# WorkFlowX_Final.net
KiCad netlist of a schematic drawn in EasyEDA Pro
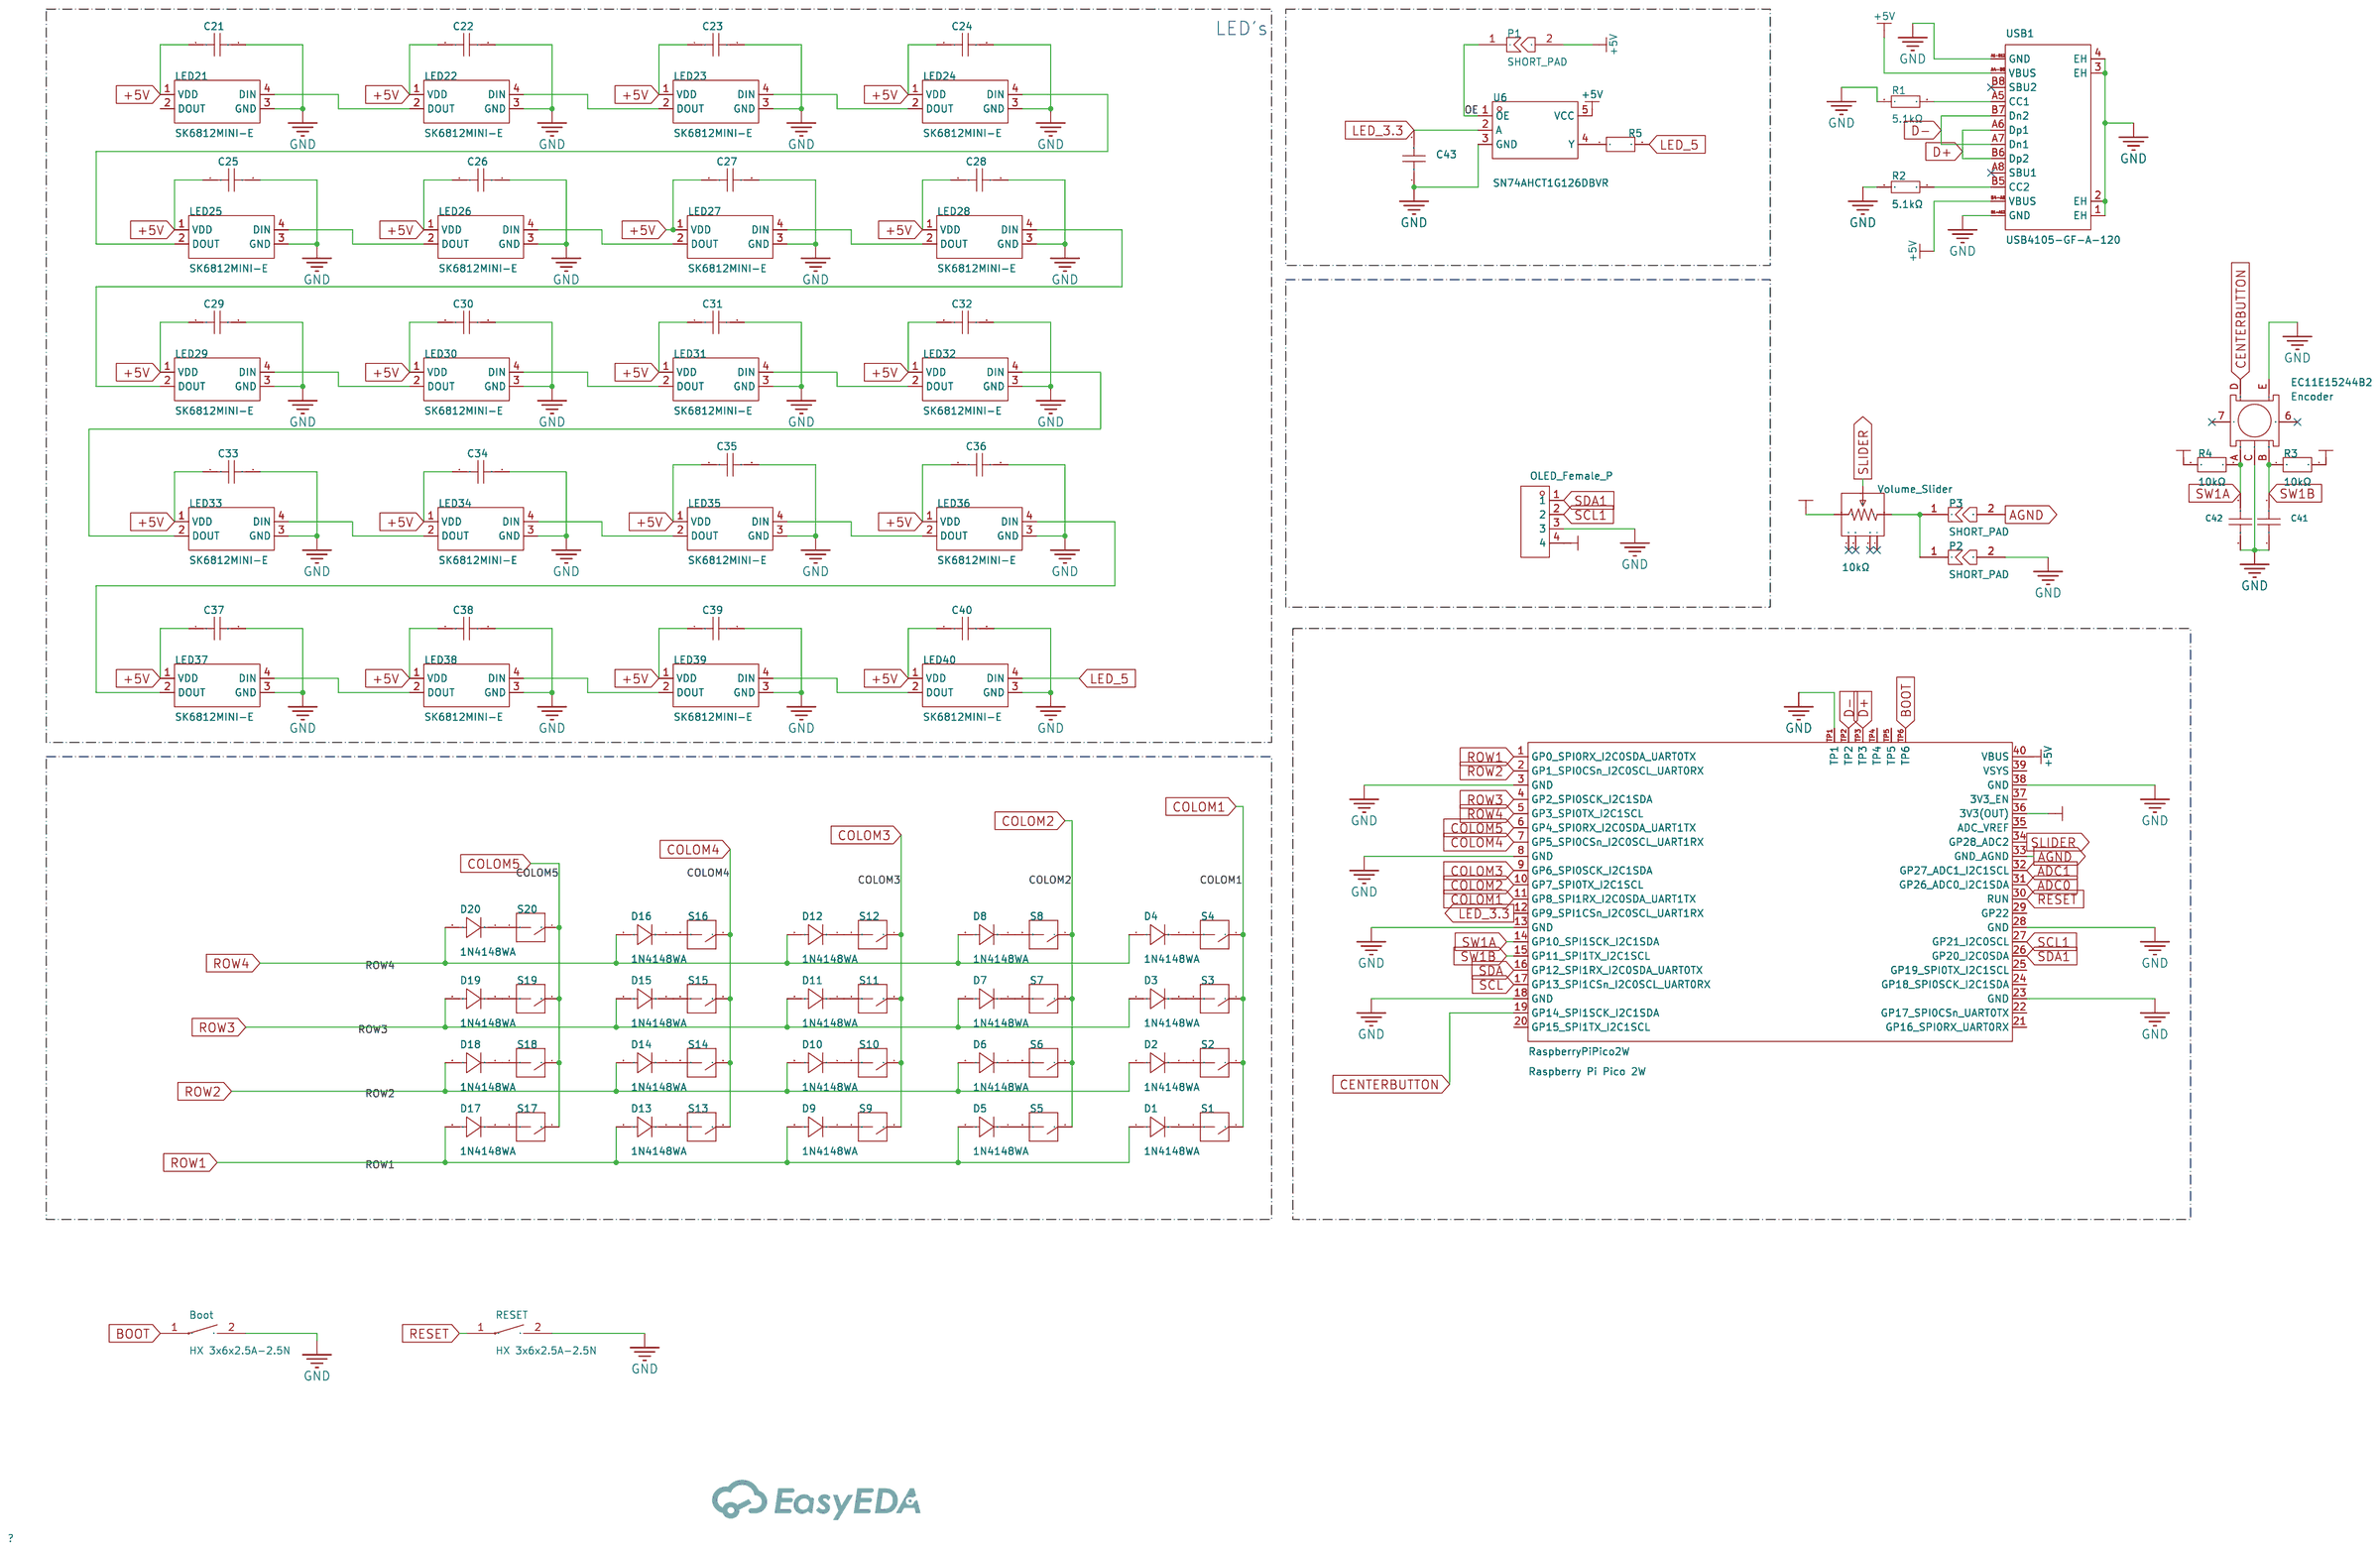
[diagram p0: schematic sheet]

(export (version "E")
  (design (tool "Eeschema 10.0.6"))
  (components
    (comp (ref "Boot")
      (value "HX 3x6x2.5A-2.5N")
      (footprint "easyedapro:SW-SMD_HX-TS-1101-C-W")
      (fields (field (name "Manufacturer") "hanxia(韩下)"))
      (libsource (lib "easyedapro") (part "HX TS-1101-C-W"))
    )
    (comp (ref "C21")
      (value "100nF")
      (footprint "easyedapro:C0603")
      (description "Capacitance:100nF Tolerance:±10% Tolerance:±10% Voltage Rating:50V Temperature Coefficient:X7R")
      (fields
        (field (name "Manufacturer Part") "CC0805KRX7R9BB104")
        (field (name "Manufacturer") "YAGEO(国巨)")
      )
      (libsource (lib "easyedapro") (part "NL0603B104M500CPBN"))
    )
    (comp (ref "C22")
      (value "100nF")
      (footprint "easyedapro:C0603")
      (description "Capacitance:100nF Tolerance:±10% Tolerance:±10% Voltage Rating:50V Temperature Coefficient:X7R")
      (fields
        (field (name "Manufacturer Part") "CC0805KRX7R9BB104")
        (field (name "Manufacturer") "YAGEO(国巨)")
      )
      (libsource (lib "easyedapro") (part "NL0603B104M500CPBN"))
    )
    (comp (ref "C23")
      (value "100nF")
      (footprint "easyedapro:C0603")
      (description "Capacitance:100nF Tolerance:±10% Tolerance:±10% Voltage Rating:50V Temperature Coefficient:X7R")
      (fields
        (field (name "Manufacturer Part") "CC0805KRX7R9BB104")
        (field (name "Manufacturer") "YAGEO(国巨)")
      )
      (libsource (lib "easyedapro") (part "NL0603B104M500CPBN"))
    )
    (comp (ref "C24")
      (value "100nF")
      (footprint "easyedapro:C0603")
      (description "Capacitance:100nF Tolerance:±10% Tolerance:±10% Voltage Rating:50V Temperature Coefficient:X7R")
      (fields
        (field (name "Manufacturer Part") "CC0805KRX7R9BB104")
        (field (name "Manufacturer") "YAGEO(国巨)")
      )
      (libsource (lib "easyedapro") (part "NL0603B104M500CPBN"))
    )
    (comp (ref "C25")
      (value "100nF")
      (footprint "easyedapro:C0603")
      (description "Capacitance:100nF Tolerance:±10% Tolerance:±10% Voltage Rating:50V Temperature Coefficient:X7R")
      (fields
        (field (name "Manufacturer Part") "CC0805KRX7R9BB104")
        (field (name "Manufacturer") "YAGEO(国巨)")
      )
      (libsource (lib "easyedapro") (part "NL0603B104M500CPBN"))
    )
    (comp (ref "C26")
      (value "100nF")
      (footprint "easyedapro:C0603")
      (description "Capacitance:100nF Tolerance:±10% Tolerance:±10% Voltage Rating:50V Temperature Coefficient:X7R")
      (fields
        (field (name "Manufacturer Part") "CC0805KRX7R9BB104")
        (field (name "Manufacturer") "YAGEO(国巨)")
      )
      (libsource (lib "easyedapro") (part "NL0603B104M500CPBN"))
    )
    (comp (ref "C27")
      (value "100nF")
      (footprint "easyedapro:C0603")
      (description "Capacitance:100nF Tolerance:±10% Tolerance:±10% Voltage Rating:50V Temperature Coefficient:X7R")
      (fields
        (field (name "Manufacturer Part") "CC0805KRX7R9BB104")
        (field (name "Manufacturer") "YAGEO(国巨)")
      )
      (libsource (lib "easyedapro") (part "NL0603B104M500CPBN"))
    )
    (comp (ref "C28")
      (value "100nF")
      (footprint "easyedapro:C0603")
      (description "Capacitance:100nF Tolerance:±10% Tolerance:±10% Voltage Rating:50V Temperature Coefficient:X7R")
      (fields
        (field (name "Manufacturer Part") "CC0805KRX7R9BB104")
        (field (name "Manufacturer") "YAGEO(国巨)")
      )
      (libsource (lib "easyedapro") (part "NL0603B104M500CPBN"))
    )
    (comp (ref "C29")
      (value "100nF")
      (footprint "easyedapro:C0603")
      (description "Capacitance:100nF Tolerance:±10% Tolerance:±10% Voltage Rating:50V Temperature Coefficient:X7R")
      (fields
        (field (name "Manufacturer Part") "CC0805KRX7R9BB104")
        (field (name "Manufacturer") "YAGEO(国巨)")
      )
      (libsource (lib "easyedapro") (part "NL0603B104M500CPBN"))
    )
    (comp (ref "C30")
      (value "100nF")
      (footprint "easyedapro:C0603")
      (description "Capacitance:100nF Tolerance:±10% Tolerance:±10% Voltage Rating:50V Temperature Coefficient:X7R")
      (fields
        (field (name "Manufacturer Part") "CC0805KRX7R9BB104")
        (field (name "Manufacturer") "YAGEO(国巨)")
      )
      (libsource (lib "easyedapro") (part "NL0603B104M500CPBN"))
    )
    (comp (ref "C31")
      (value "100nF")
      (footprint "easyedapro:C0603")
      (description "Capacitance:100nF Tolerance:±10% Tolerance:±10% Voltage Rating:50V Temperature Coefficient:X7R")
      (fields
        (field (name "Manufacturer Part") "CC0805KRX7R9BB104")
        (field (name "Manufacturer") "YAGEO(国巨)")
      )
      (libsource (lib "easyedapro") (part "NL0603B104M500CPBN"))
    )
    (comp (ref "C32")
      (value "100nF")
      (footprint "easyedapro:C0603")
      (description "Capacitance:100nF Tolerance:±10% Tolerance:±10% Voltage Rating:50V Temperature Coefficient:X7R")
      (fields
        (field (name "Manufacturer Part") "CC0805KRX7R9BB104")
        (field (name "Manufacturer") "YAGEO(国巨)")
      )
      (libsource (lib "easyedapro") (part "NL0603B104M500CPBN"))
    )
    (comp (ref "C33")
      (value "100nF")
      (footprint "easyedapro:C0603")
      (description "Capacitance:100nF Tolerance:±10% Tolerance:±10% Voltage Rating:50V Temperature Coefficient:X7R")
      (fields
        (field (name "Manufacturer Part") "CC0805KRX7R9BB104")
        (field (name "Manufacturer") "YAGEO(国巨)")
      )
      (libsource (lib "easyedapro") (part "NL0603B104M500CPBN"))
    )
    (comp (ref "C34")
      (value "100nF")
      (footprint "easyedapro:C0603")
      (description "Capacitance:100nF Tolerance:±10% Tolerance:±10% Voltage Rating:50V Temperature Coefficient:X7R")
      (fields
        (field (name "Manufacturer Part") "CC0805KRX7R9BB104")
        (field (name "Manufacturer") "YAGEO(国巨)")
      )
      (libsource (lib "easyedapro") (part "NL0603B104M500CPBN"))
    )
    (comp (ref "C35")
      (value "100nF")
      (footprint "easyedapro:C0603")
      (description "Capacitance:100nF Tolerance:±10% Tolerance:±10% Voltage Rating:50V Temperature Coefficient:X7R")
      (fields
        (field (name "Manufacturer Part") "CC0805KRX7R9BB104")
        (field (name "Manufacturer") "YAGEO(国巨)")
      )
      (libsource (lib "easyedapro") (part "NL0603B104M500CPBN"))
    )
    (comp (ref "C36")
      (value "100nF")
      (footprint "easyedapro:C0603")
      (description "Capacitance:100nF Tolerance:±10% Tolerance:±10% Voltage Rating:50V Temperature Coefficient:X7R")
      (fields
        (field (name "Manufacturer Part") "CC0805KRX7R9BB104")
        (field (name "Manufacturer") "YAGEO(国巨)")
      )
      (libsource (lib "easyedapro") (part "NL0603B104M500CPBN"))
    )
    (comp (ref "C37")
      (value "100nF")
      (footprint "easyedapro:C0603")
      (description "Capacitance:100nF Tolerance:±10% Tolerance:±10% Voltage Rating:50V Temperature Coefficient:X7R")
      (fields
        (field (name "Manufacturer Part") "CC0805KRX7R9BB104")
        (field (name "Manufacturer") "YAGEO(国巨)")
      )
      (libsource (lib "easyedapro") (part "NL0603B104M500CPBN"))
    )
    (comp (ref "C38")
      (value "100nF")
      (footprint "easyedapro:C0603")
      (description "Capacitance:100nF Tolerance:±10% Tolerance:±10% Voltage Rating:50V Temperature Coefficient:X7R")
      (fields
        (field (name "Manufacturer Part") "CC0805KRX7R9BB104")
        (field (name "Manufacturer") "YAGEO(国巨)")
      )
      (libsource (lib "easyedapro") (part "NL0603B104M500CPBN"))
    )
    (comp (ref "C39")
      (value "100nF")
      (footprint "easyedapro:C0603")
      (description "Capacitance:100nF Tolerance:±10% Tolerance:±10% Voltage Rating:50V Temperature Coefficient:X7R")
      (fields
        (field (name "Manufacturer Part") "CC0805KRX7R9BB104")
        (field (name "Manufacturer") "YAGEO(国巨)")
      )
      (libsource (lib "easyedapro") (part "NL0603B104M500CPBN"))
    )
    (comp (ref "C40")
      (value "100nF")
      (footprint "easyedapro:C0603")
      (description "Capacitance:100nF Tolerance:±10% Tolerance:±10% Voltage Rating:50V Temperature Coefficient:X7R")
      (fields
        (field (name "Manufacturer Part") "CC0805KRX7R9BB104")
        (field (name "Manufacturer") "YAGEO(国巨)")
      )
      (libsource (lib "easyedapro") (part "NL0603B104M500CPBN"))
    )
    (comp (ref "C41")
      (value "100nF")
      (footprint "easyedapro:C0805")
      (description "Capacitance:100nF Tolerance:±10% Tolerance:±10% Voltage Rating:50V Temperature Coefficient:X7R")
      (fields
        (field (name "Manufacturer Part") "CC0805KRX7R9BB104")
        (field (name "Manufacturer") "YAGEO(国巨)")
      )
      (libsource (lib "easyedapro") (part "CC0805JRX7R9BB103"))
    )
    (comp (ref "C42")
      (value "100nF")
      (footprint "easyedapro:C0805")
      (description "Capacitance:100nF Tolerance:±10% Tolerance:±10% Voltage Rating:50V Temperature Coefficient:X7R")
      (fields
        (field (name "Manufacturer Part") "CC0805KRX7R9BB104")
        (field (name "Manufacturer") "YAGEO(国巨)")
      )
      (libsource (lib "easyedapro") (part "CC0805JRX7R9BB103"))
    )
    (comp (ref "C43")
      (value "100nF")
      (footprint "easyedapro:C0603")
      (description "Capacitance:100nF Tolerance:±10% Tolerance:±10% Voltage Rating:50V Temperature Coefficient:X7R")
      (fields
        (field (name "Manufacturer Part") "CC0805KRX7R9BB104")
        (field (name "Manufacturer") "YAGEO(国巨)")
      )
      (libsource (lib "easyedapro") (part "NL0603B104M500CPBN"))
    )
    (comp (ref "D1")
      (value "1N4148WA")
      (footprint "easyedapro:SOD-323_L1.7-W1.3-LS2.7-RD")
      (fields (field (name "Manufacturer") "PJSEMI(平晶微)"))
      (libsource (lib "easyedapro") (part "1N4148WS_C5381436"))
    )
    (comp (ref "D2")
      (value "1N4148WA")
      (footprint "easyedapro:SOD-323_L1.7-W1.3-LS2.7-RD")
      (fields (field (name "Manufacturer") "PJSEMI(平晶微)"))
      (libsource (lib "easyedapro") (part "1N4148WS_C5381436"))
    )
    (comp (ref "D3")
      (value "1N4148WA")
      (footprint "easyedapro:SOD-323_L1.7-W1.3-LS2.7-RD")
      (fields (field (name "Manufacturer") "PJSEMI(平晶微)"))
      (libsource (lib "easyedapro") (part "1N4148WS_C5381436"))
    )
    (comp (ref "D4")
      (value "1N4148WA")
      (footprint "easyedapro:SOD-323_L1.7-W1.3-LS2.7-RD")
      (fields (field (name "Manufacturer") "PJSEMI(平晶微)"))
      (libsource (lib "easyedapro") (part "1N4148WS_C5381436"))
    )
    (comp (ref "D5")
      (value "1N4148WA")
      (footprint "easyedapro:SOD-323_L1.7-W1.3-LS2.7-RD")
      (fields (field (name "Manufacturer") "PJSEMI(平晶微)"))
      (libsource (lib "easyedapro") (part "1N4148WS_C5381436"))
    )
    (comp (ref "D6")
      (value "1N4148WA")
      (footprint "easyedapro:SOD-323_L1.7-W1.3-LS2.7-RD")
      (fields (field (name "Manufacturer") "PJSEMI(平晶微)"))
      (libsource (lib "easyedapro") (part "1N4148WS_C5381436"))
    )
    (comp (ref "D7")
      (value "1N4148WA")
      (footprint "easyedapro:SOD-323_L1.7-W1.3-LS2.7-RD")
      (fields (field (name "Manufacturer") "PJSEMI(平晶微)"))
      (libsource (lib "easyedapro") (part "1N4148WS_C5381436"))
    )
    (comp (ref "D8")
      (value "1N4148WA")
      (footprint "easyedapro:SOD-323_L1.7-W1.3-LS2.7-RD")
      (fields (field (name "Manufacturer") "PJSEMI(平晶微)"))
      (libsource (lib "easyedapro") (part "1N4148WS_C5381436"))
    )
    (comp (ref "D9")
      (value "1N4148WA")
      (footprint "easyedapro:SOD-323_L1.7-W1.3-LS2.7-RD")
      (fields (field (name "Manufacturer") "PJSEMI(平晶微)"))
      (libsource (lib "easyedapro") (part "1N4148WS_C5381436"))
    )
    (comp (ref "D10")
      (value "1N4148WA")
      (footprint "easyedapro:SOD-323_L1.7-W1.3-LS2.7-RD")
      (fields (field (name "Manufacturer") "PJSEMI(平晶微)"))
      (libsource (lib "easyedapro") (part "1N4148WS_C5381436"))
    )
    (comp (ref "D11")
      (value "1N4148WA")
      (footprint "easyedapro:SOD-323_L1.7-W1.3-LS2.7-RD")
      (fields (field (name "Manufacturer") "PJSEMI(平晶微)"))
      (libsource (lib "easyedapro") (part "1N4148WS_C5381436"))
    )
    (comp (ref "D12")
      (value "1N4148WA")
      (footprint "easyedapro:SOD-323_L1.7-W1.3-LS2.7-RD")
      (fields (field (name "Manufacturer") "PJSEMI(平晶微)"))
      (libsource (lib "easyedapro") (part "1N4148WS_C5381436"))
    )
    (comp (ref "D13")
      (value "1N4148WA")
      (footprint "easyedapro:SOD-323_L1.7-W1.3-LS2.7-RD")
      (fields (field (name "Manufacturer") "PJSEMI(平晶微)"))
      (libsource (lib "easyedapro") (part "1N4148WS_C5381436"))
    )
    (comp (ref "D14")
      (value "1N4148WA")
      (footprint "easyedapro:SOD-323_L1.7-W1.3-LS2.7-RD")
      (fields (field (name "Manufacturer") "PJSEMI(平晶微)"))
      (libsource (lib "easyedapro") (part "1N4148WS_C5381436"))
    )
    (comp (ref "D15")
      (value "1N4148WA")
      (footprint "easyedapro:SOD-323_L1.7-W1.3-LS2.7-RD")
      (fields (field (name "Manufacturer") "PJSEMI(平晶微)"))
      (libsource (lib "easyedapro") (part "1N4148WS_C5381436"))
    )
    (comp (ref "D16")
      (value "1N4148WA")
      (footprint "easyedapro:SOD-323_L1.7-W1.3-LS2.7-RD")
      (fields (field (name "Manufacturer") "PJSEMI(平晶微)"))
      (libsource (lib "easyedapro") (part "1N4148WS_C5381436"))
    )
    (comp (ref "D17")
      (value "1N4148WA")
      (footprint "easyedapro:SOD-323_L1.7-W1.3-LS2.7-RD")
      (fields (field (name "Manufacturer") "PJSEMI(平晶微)"))
      (libsource (lib "easyedapro") (part "1N4148WS_C5381436"))
    )
    (comp (ref "D18")
      (value "1N4148WA")
      (footprint "easyedapro:SOD-323_L1.7-W1.3-LS2.7-RD")
      (fields (field (name "Manufacturer") "PJSEMI(平晶微)"))
      (libsource (lib "easyedapro") (part "1N4148WS_C5381436"))
    )
    (comp (ref "D19")
      (value "1N4148WA")
      (footprint "easyedapro:SOD-323_L1.7-W1.3-LS2.7-RD")
      (fields (field (name "Manufacturer") "PJSEMI(平晶微)"))
      (libsource (lib "easyedapro") (part "1N4148WS_C5381436"))
    )
    (comp (ref "D20")
      (value "1N4148WA")
      (footprint "easyedapro:SOD-323_L1.7-W1.3-LS2.7-RD")
      (fields (field (name "Manufacturer") "PJSEMI(平晶微)"))
      (libsource (lib "easyedapro") (part "1N4148WS_C5381436"))
    )
    (comp (ref "Encoder")
      (value "EC11E15244B2")
      (footprint "easyedapro:SW-TH_EC11XXXXXXXX")
      (fields (field (name "Manufacturer") "ALPSALPINE(阿尔卑斯阿尔派)"))
      (libsource (lib "easyedapro") (part "EC11E15204A3"))
    )
    (comp (ref "LED21")
      (value "SK6812MINI-E")
      (footprint "easyedapro:LED-SMD_L3.2-W2.8-LS5.9_SK6812MINI-E")
      (fields (field (name "Manufacturer") "欧思科光电"))
      (libsource (lib "easyedapro") (part "SK6812MINI-E_C5149201"))
    )
    (comp (ref "LED22")
      (value "SK6812MINI-E")
      (footprint "easyedapro:LED-SMD_L3.2-W2.8-LS5.9_SK6812MINI-E")
      (fields (field (name "Manufacturer") "欧思科光电"))
      (libsource (lib "easyedapro") (part "SK6812MINI-E_C5149201"))
    )
    (comp (ref "LED23")
      (value "SK6812MINI-E")
      (footprint "easyedapro:LED-SMD_L3.2-W2.8-LS5.9_SK6812MINI-E")
      (fields (field (name "Manufacturer") "欧思科光电"))
      (libsource (lib "easyedapro") (part "SK6812MINI-E_C5149201"))
    )
    (comp (ref "LED24")
      (value "SK6812MINI-E")
      (footprint "easyedapro:LED-SMD_L3.2-W2.8-LS5.9_SK6812MINI-E")
      (fields (field (name "Manufacturer") "欧思科光电"))
      (libsource (lib "easyedapro") (part "SK6812MINI-E_C5149201"))
    )
    (comp (ref "LED25")
      (value "SK6812MINI-E")
      (footprint "easyedapro:LED-SMD_L3.2-W2.8-LS5.9_SK6812MINI-E")
      (fields (field (name "Manufacturer") "欧思科光电"))
      (libsource (lib "easyedapro") (part "SK6812MINI-E_C5149201"))
    )
    (comp (ref "LED26")
      (value "SK6812MINI-E")
      (footprint "easyedapro:LED-SMD_L3.2-W2.8-LS5.9_SK6812MINI-E")
      (fields (field (name "Manufacturer") "欧思科光电"))
      (libsource (lib "easyedapro") (part "SK6812MINI-E_C5149201"))
    )
    (comp (ref "LED27")
      (value "SK6812MINI-E")
      (footprint "easyedapro:LED-SMD_L3.2-W2.8-LS5.9_SK6812MINI-E")
      (fields (field (name "Manufacturer") "欧思科光电"))
      (libsource (lib "easyedapro") (part "SK6812MINI-E_C5149201"))
    )
    (comp (ref "LED28")
      (value "SK6812MINI-E")
      (footprint "easyedapro:LED-SMD_L3.2-W2.8-LS5.9_SK6812MINI-E")
      (fields (field (name "Manufacturer") "欧思科光电"))
      (libsource (lib "easyedapro") (part "SK6812MINI-E_C5149201"))
    )
    (comp (ref "LED29")
      (value "SK6812MINI-E")
      (footprint "easyedapro:LED-SMD_L3.2-W2.8-LS5.9_SK6812MINI-E")
      (fields (field (name "Manufacturer") "欧思科光电"))
      (libsource (lib "easyedapro") (part "SK6812MINI-E_C5149201"))
    )
    (comp (ref "LED30")
      (value "SK6812MINI-E")
      (footprint "easyedapro:LED-SMD_L3.2-W2.8-LS5.9_SK6812MINI-E")
      (fields (field (name "Manufacturer") "欧思科光电"))
      (libsource (lib "easyedapro") (part "SK6812MINI-E_C5149201"))
    )
    (comp (ref "LED31")
      (value "SK6812MINI-E")
      (footprint "easyedapro:LED-SMD_L3.2-W2.8-LS5.9_SK6812MINI-E")
      (fields (field (name "Manufacturer") "欧思科光电"))
      (libsource (lib "easyedapro") (part "SK6812MINI-E_C5149201"))
    )
    (comp (ref "LED32")
      (value "SK6812MINI-E")
      (footprint "easyedapro:LED-SMD_L3.2-W2.8-LS5.9_SK6812MINI-E")
      (fields (field (name "Manufacturer") "欧思科光电"))
      (libsource (lib "easyedapro") (part "SK6812MINI-E_C5149201"))
    )
    (comp (ref "LED33")
      (value "SK6812MINI-E")
      (footprint "easyedapro:LED-SMD_L3.2-W2.8-LS5.9_SK6812MINI-E")
      (fields (field (name "Manufacturer") "欧思科光电"))
      (libsource (lib "easyedapro") (part "SK6812MINI-E_C5149201"))
    )
    (comp (ref "LED34")
      (value "SK6812MINI-E")
      (footprint "easyedapro:LED-SMD_L3.2-W2.8-LS5.9_SK6812MINI-E")
      (fields (field (name "Manufacturer") "欧思科光电"))
      (libsource (lib "easyedapro") (part "SK6812MINI-E_C5149201"))
    )
    (comp (ref "LED35")
      (value "SK6812MINI-E")
      (footprint "easyedapro:LED-SMD_L3.2-W2.8-LS5.9_SK6812MINI-E")
      (fields (field (name "Manufacturer") "欧思科光电"))
      (libsource (lib "easyedapro") (part "SK6812MINI-E_C5149201"))
    )
    (comp (ref "LED36")
      (value "SK6812MINI-E")
      (footprint "easyedapro:LED-SMD_L3.2-W2.8-LS5.9_SK6812MINI-E")
      (fields (field (name "Manufacturer") "欧思科光电"))
      (libsource (lib "easyedapro") (part "SK6812MINI-E_C5149201"))
    )
    (comp (ref "LED37")
      (value "SK6812MINI-E")
      (footprint "easyedapro:LED-SMD_L3.2-W2.8-LS5.9_SK6812MINI-E")
      (fields (field (name "Manufacturer") "欧思科光电"))
      (libsource (lib "easyedapro") (part "SK6812MINI-E_C5149201"))
    )
    (comp (ref "LED38")
      (value "SK6812MINI-E")
      (footprint "easyedapro:LED-SMD_L3.2-W2.8-LS5.9_SK6812MINI-E")
      (fields (field (name "Manufacturer") "欧思科光电"))
      (libsource (lib "easyedapro") (part "SK6812MINI-E_C5149201"))
    )
    (comp (ref "LED39")
      (value "SK6812MINI-E")
      (footprint "easyedapro:LED-SMD_L3.2-W2.8-LS5.9_SK6812MINI-E")
      (fields (field (name "Manufacturer") "欧思科光电"))
      (libsource (lib "easyedapro") (part "SK6812MINI-E_C5149201"))
    )
    (comp (ref "LED40")
      (value "SK6812MINI-E")
      (footprint "easyedapro:LED-SMD_L3.2-W2.8-LS5.9_SK6812MINI-E")
      (fields (field (name "Manufacturer") "欧思科光电"))
      (libsource (lib "easyedapro") (part "SK6812MINI-E_C5149201"))
    )
    (comp (ref "OLED_Female_P")
      (value "~")
      (footprint "easyedapro:CONN-TH_4P-P2.50-XH2.54-4P")
      (fields (field (name "Manufacturer Part") "XH-2.54-4P"))
      (libsource (lib "easyedapro") (part "XH-2.54-4P"))
    )
    (comp (ref "P1")
      (value "SHORT_PAD")
      (footprint "easyedapro:SHORT_PAD")
      (libsource (lib "easyedapro") (part "SHORT_PAD"))
    )
    (comp (ref "P2")
      (value "SHORT_PAD")
      (footprint "easyedapro:SHORT_PAD")
      (libsource (lib "easyedapro") (part "SHORT_PAD"))
    )
    (comp (ref "P3")
      (value "SHORT_PAD")
      (footprint "easyedapro:SHORT_PAD")
      (libsource (lib "easyedapro") (part "SHORT_PAD"))
    )
    (comp (ref "R1")
      (value "5.1kΩ")
      (footprint "easyedapro:R0805")
      (fields (field (name "Manufacturer Part") "MCR10EZPF5101") (field (name "Manufacturer") "ROHM(罗姆)"))
      (libsource (lib "easyedapro") (part "MCR10EZPF5101"))
    )
    (comp (ref "R2")
      (value "5.1kΩ")
      (footprint "easyedapro:R0805")
      (fields (field (name "Manufacturer Part") "MCR10EZPF5101") (field (name "Manufacturer") "ROHM(罗姆)"))
      (libsource (lib "easyedapro") (part "MCR10EZPF5101"))
    )
    (comp (ref "R3")
      (value "10kΩ")
      (footprint "easyedapro:R0805")
      (fields (field (name "Manufacturer Part") "SCR0805J10K") (field (name "Manufacturer") "VO(翔胜)"))
      (libsource (lib "easyedapro") (part "SCR0805J10K"))
    )
    (comp (ref "R4")
      (value "10kΩ")
      (footprint "easyedapro:R0805")
      (fields (field (name "Manufacturer Part") "SCR0805J10K") (field (name "Manufacturer") "VO(翔胜)"))
      (libsource (lib "easyedapro") (part "SCR0805J10K"))
    )
    (comp (ref "R5")
      (value "300Ω")
      (footprint "easyedapro:R0805")
      (fields
        (field (name "Manufacturer Part") "CRCW0805300RFKEA")
        (field (name "Manufacturer") "VISHAY(威世)")
      )
      (libsource (lib "easyedapro") (part "CRCW0805300RFKEA"))
    )
    (comp (ref "RaspberryPiPico2W")
      (value "Raspberry Pi Pico 2W")
      (footprint "easyedapro:COMM-SMD_L51.0-W21.0-P2.54_PICOW")
      (fields (field (name "Manufacturer") "Raspberry Pi(树莓派)"))
      (libsource (lib "easyedapro") (part "RASPBERRY PI PICO 2W"))
    )
    (comp (ref "RESET")
      (value "HX 3x6x2.5A-2.5N")
      (footprint "easyedapro:SW-SMD_HX-TS-1101-C-W")
      (fields (field (name "Manufacturer") "hanxia(韩下)"))
      (libsource (lib "easyedapro") (part "HX TS-1101-C-W"))
    )
    (comp (ref "S1")
      (value "adafruit_electromech_KBD_SWITCH_KAILH_SOCKET_BOX_JADE_KAILH_SOCKET")
      (footprint "easyedapro:KAILH_SOCKET")
      (libsource (lib "easyedapro") (part "adafruit_electromech_KBD_SWITCH_KAILH_SOCKET_BOX_JADE_KAILH_SOCKET"))
    )
    (comp (ref "S2")
      (value "adafruit_electromech_KBD_SWITCH_KAILH_SOCKET_BOX_JADE_KAILH_SOCKET")
      (footprint "easyedapro:KAILH_SOCKET")
      (libsource (lib "easyedapro") (part "adafruit_electromech_KBD_SWITCH_KAILH_SOCKET_BOX_JADE_KAILH_SOCKET"))
    )
    (comp (ref "S3")
      (value "adafruit_electromech_KBD_SWITCH_KAILH_SOCKET_BOX_JADE_KAILH_SOCKET")
      (footprint "easyedapro:KAILH_SOCKET")
      (libsource (lib "easyedapro") (part "adafruit_electromech_KBD_SWITCH_KAILH_SOCKET_BOX_JADE_KAILH_SOCKET"))
    )
    (comp (ref "S4")
      (value "adafruit_electromech_KBD_SWITCH_KAILH_SOCKET_BOX_JADE_KAILH_SOCKET")
      (footprint "easyedapro:KAILH_SOCKET")
      (libsource (lib "easyedapro") (part "adafruit_electromech_KBD_SWITCH_KAILH_SOCKET_BOX_JADE_KAILH_SOCKET"))
    )
    (comp (ref "S5")
      (value "adafruit_electromech_KBD_SWITCH_KAILH_SOCKET_BOX_JADE_KAILH_SOCKET")
      (footprint "easyedapro:KAILH_SOCKET")
      (libsource (lib "easyedapro") (part "adafruit_electromech_KBD_SWITCH_KAILH_SOCKET_BOX_JADE_KAILH_SOCKET"))
    )
    (comp (ref "S6")
      (value "adafruit_electromech_KBD_SWITCH_KAILH_SOCKET_BOX_JADE_KAILH_SOCKET")
      (footprint "easyedapro:KAILH_SOCKET")
      (libsource (lib "easyedapro") (part "adafruit_electromech_KBD_SWITCH_KAILH_SOCKET_BOX_JADE_KAILH_SOCKET"))
    )
    (comp (ref "S7")
      (value "adafruit_electromech_KBD_SWITCH_KAILH_SOCKET_BOX_JADE_KAILH_SOCKET")
      (footprint "easyedapro:KAILH_SOCKET")
      (libsource (lib "easyedapro") (part "adafruit_electromech_KBD_SWITCH_KAILH_SOCKET_BOX_JADE_KAILH_SOCKET"))
    )
    (comp (ref "S8")
      (value "adafruit_electromech_KBD_SWITCH_KAILH_SOCKET_BOX_JADE_KAILH_SOCKET")
      (footprint "easyedapro:KAILH_SOCKET")
      (libsource (lib "easyedapro") (part "adafruit_electromech_KBD_SWITCH_KAILH_SOCKET_BOX_JADE_KAILH_SOCKET"))
    )
    (comp (ref "S9")
      (value "adafruit_electromech_KBD_SWITCH_KAILH_SOCKET_BOX_JADE_KAILH_SOCKET")
      (footprint "easyedapro:KAILH_SOCKET")
      (libsource (lib "easyedapro") (part "adafruit_electromech_KBD_SWITCH_KAILH_SOCKET_BOX_JADE_KAILH_SOCKET"))
    )
    (comp (ref "S10")
      (value "adafruit_electromech_KBD_SWITCH_KAILH_SOCKET_BOX_JADE_KAILH_SOCKET")
      (footprint "easyedapro:KAILH_SOCKET")
      (libsource (lib "easyedapro") (part "adafruit_electromech_KBD_SWITCH_KAILH_SOCKET_BOX_JADE_KAILH_SOCKET"))
    )
    (comp (ref "S11")
      (value "adafruit_electromech_KBD_SWITCH_KAILH_SOCKET_BOX_JADE_KAILH_SOCKET")
      (footprint "easyedapro:KAILH_SOCKET")
      (libsource (lib "easyedapro") (part "adafruit_electromech_KBD_SWITCH_KAILH_SOCKET_BOX_JADE_KAILH_SOCKET"))
    )
    (comp (ref "S12")
      (value "adafruit_electromech_KBD_SWITCH_KAILH_SOCKET_BOX_JADE_KAILH_SOCKET")
      (footprint "easyedapro:KAILH_SOCKET")
      (libsource (lib "easyedapro") (part "adafruit_electromech_KBD_SWITCH_KAILH_SOCKET_BOX_JADE_KAILH_SOCKET"))
    )
    (comp (ref "S13")
      (value "adafruit_electromech_KBD_SWITCH_KAILH_SOCKET_BOX_JADE_KAILH_SOCKET")
      (footprint "easyedapro:KAILH_SOCKET")
      (libsource (lib "easyedapro") (part "adafruit_electromech_KBD_SWITCH_KAILH_SOCKET_BOX_JADE_KAILH_SOCKET"))
    )
    (comp (ref "S14")
      (value "adafruit_electromech_KBD_SWITCH_KAILH_SOCKET_BOX_JADE_KAILH_SOCKET")
      (footprint "easyedapro:KAILH_SOCKET")
      (libsource (lib "easyedapro") (part "adafruit_electromech_KBD_SWITCH_KAILH_SOCKET_BOX_JADE_KAILH_SOCKET"))
    )
    (comp (ref "S15")
      (value "adafruit_electromech_KBD_SWITCH_KAILH_SOCKET_BOX_JADE_KAILH_SOCKET")
      (footprint "easyedapro:KAILH_SOCKET")
      (libsource (lib "easyedapro") (part "adafruit_electromech_KBD_SWITCH_KAILH_SOCKET_BOX_JADE_KAILH_SOCKET"))
    )
    (comp (ref "S16")
      (value "adafruit_electromech_KBD_SWITCH_KAILH_SOCKET_BOX_JADE_KAILH_SOCKET")
      (footprint "easyedapro:KAILH_SOCKET")
      (libsource (lib "easyedapro") (part "adafruit_electromech_KBD_SWITCH_KAILH_SOCKET_BOX_JADE_KAILH_SOCKET"))
    )
    (comp (ref "S17")
      (value "adafruit_electromech_KBD_SWITCH_KAILH_SOCKET_BOX_JADE_KAILH_SOCKET")
      (footprint "easyedapro:KAILH_SOCKET")
      (libsource (lib "easyedapro") (part "adafruit_electromech_KBD_SWITCH_KAILH_SOCKET_BOX_JADE_KAILH_SOCKET"))
    )
    (comp (ref "S18")
      (value "adafruit_electromech_KBD_SWITCH_KAILH_SOCKET_BOX_JADE_KAILH_SOCKET")
      (footprint "easyedapro:KAILH_SOCKET")
      (libsource (lib "easyedapro") (part "adafruit_electromech_KBD_SWITCH_KAILH_SOCKET_BOX_JADE_KAILH_SOCKET"))
    )
    (comp (ref "S19")
      (value "adafruit_electromech_KBD_SWITCH_KAILH_SOCKET_BOX_JADE_KAILH_SOCKET")
      (footprint "easyedapro:KAILH_SOCKET")
      (libsource (lib "easyedapro") (part "adafruit_electromech_KBD_SWITCH_KAILH_SOCKET_BOX_JADE_KAILH_SOCKET"))
    )
    (comp (ref "S20")
      (value "adafruit_electromech_KBD_SWITCH_KAILH_SOCKET_BOX_JADE_KAILH_SOCKET")
      (footprint "easyedapro:KAILH_SOCKET")
      (libsource (lib "easyedapro") (part "adafruit_electromech_KBD_SWITCH_KAILH_SOCKET_BOX_JADE_KAILH_SOCKET"))
    )
    (comp (ref "U6")
      (value "SN74AHCT1G126DBVR")
      (footprint "easyedapro:SOT-23-5_L3.0-W1.7-P0.95-LS2.8-BR")
      (fields (field (name "Manufacturer") "TI(德州仪器)"))
      (libsource (lib "easyedapro") (part "SN74AHCT1G126DBVR"))
    )
    (comp (ref "USB1")
      (value "USB4105-GF-A-120")
      (footprint "easyedapro:USB-C-SMD_MC-311D")
      (fields (field (name "Manufacturer") "GCT"))
      (libsource (lib "easyedapro") (part "USB4105-GF-A-120"))
    )
    (comp (ref "Volume_Slider")
      (value "10kΩ")
      (footprint "easyedapro:RES-ADJ-TH_PTA6043-2015DPB103")
      (description "Resistance:10kΩ Tolerance:±20% Tolerance:±20% Power(Watts):250mW")
      (fields (field (name "Manufacturer Part") "PTA6043-2015DPB103") (field (name "Manufacturer") "BOURNS"))
      (libsource (lib "easyedapro") (part "PTA6043-2015DPB103"))
    )
  )
  (nets
    (net (code "1") (name "+3.3V") (class "Default")
      (node (ref "OLED_Female_P") (pin "4") (pinfunction "4_4") (pintype "input"))
      (node (ref "R3") (pin "2") (pinfunction "2_2") (pintype "unspecified"))
      (node (ref "R4") (pin "1") (pinfunction "1_1") (pintype "unspecified"))
      (node (ref "RaspberryPiPico2W") (pin "36") (pinfunction "3V3(OUT)_36") (pintype "unspecified"))
      (node (ref "Volume_Slider") (pin "3") (pinfunction "3_3") (pintype "unspecified"))
    )
    (net (code "2") (name "+5V") (class "Default")
      (node (ref "C21") (pin "1") (pinfunction "1_1") (pintype "unspecified"))
      (node (ref "C22") (pin "1") (pinfunction "1_1") (pintype "unspecified"))
      (node (ref "C23") (pin "1") (pinfunction "1_1") (pintype "unspecified"))
      (node (ref "C24") (pin "1") (pinfunction "1_1") (pintype "unspecified"))
      (node (ref "C25") (pin "1") (pinfunction "1_1") (pintype "unspecified"))
      (node (ref "C26") (pin "1") (pinfunction "1_1") (pintype "unspecified"))
      (node (ref "C27") (pin "1") (pinfunction "1_1") (pintype "unspecified"))
      (node (ref "C28") (pin "1") (pinfunction "1_1") (pintype "unspecified"))
      (node (ref "C29") (pin "1") (pinfunction "1_1") (pintype "unspecified"))
      (node (ref "C30") (pin "1") (pinfunction "1_1") (pintype "unspecified"))
      (node (ref "C31") (pin "1") (pinfunction "1_1") (pintype "unspecified"))
      (node (ref "C32") (pin "1") (pinfunction "1_1") (pintype "unspecified"))
      (node (ref "C33") (pin "1") (pinfunction "1_1") (pintype "unspecified"))
      (node (ref "C34") (pin "1") (pinfunction "1_1") (pintype "unspecified"))
      (node (ref "C35") (pin "1") (pinfunction "1_1") (pintype "unspecified"))
      (node (ref "C36") (pin "1") (pinfunction "1_1") (pintype "unspecified"))
      (node (ref "C37") (pin "1") (pinfunction "1_1") (pintype "unspecified"))
      (node (ref "C38") (pin "1") (pinfunction "1_1") (pintype "unspecified"))
      (node (ref "C39") (pin "1") (pinfunction "1_1") (pintype "unspecified"))
      (node (ref "C40") (pin "1") (pinfunction "1_1") (pintype "unspecified"))
      (node (ref "LED21") (pin "1") (pinfunction "VDD_1") (pintype "unspecified"))
      (node (ref "LED22") (pin "1") (pinfunction "VDD_1") (pintype "unspecified"))
      (node (ref "LED23") (pin "1") (pinfunction "VDD_1") (pintype "unspecified"))
      (node (ref "LED24") (pin "1") (pinfunction "VDD_1") (pintype "unspecified"))
      (node (ref "LED25") (pin "1") (pinfunction "VDD_1") (pintype "unspecified"))
      (node (ref "LED26") (pin "1") (pinfunction "VDD_1") (pintype "unspecified"))
      (node (ref "LED27") (pin "1") (pinfunction "VDD_1") (pintype "unspecified"))
      (node (ref "LED28") (pin "1") (pinfunction "VDD_1") (pintype "unspecified"))
      (node (ref "LED29") (pin "1") (pinfunction "VDD_1") (pintype "unspecified"))
      (node (ref "LED30") (pin "1") (pinfunction "VDD_1") (pintype "unspecified"))
      (node (ref "LED31") (pin "1") (pinfunction "VDD_1") (pintype "unspecified"))
      (node (ref "LED32") (pin "1") (pinfunction "VDD_1") (pintype "unspecified"))
      (node (ref "LED33") (pin "1") (pinfunction "VDD_1") (pintype "unspecified"))
      (node (ref "LED34") (pin "1") (pinfunction "VDD_1") (pintype "unspecified"))
      (node (ref "LED35") (pin "1") (pinfunction "VDD_1") (pintype "unspecified"))
      (node (ref "LED36") (pin "1") (pinfunction "VDD_1") (pintype "unspecified"))
      (node (ref "LED37") (pin "1") (pinfunction "VDD_1") (pintype "unspecified"))
      (node (ref "LED38") (pin "1") (pinfunction "VDD_1") (pintype "unspecified"))
      (node (ref "LED39") (pin "1") (pinfunction "VDD_1") (pintype "unspecified"))
      (node (ref "LED40") (pin "1") (pinfunction "VDD_1") (pintype "unspecified"))
      (node (ref "P1") (pin "2") (pinfunction "2_2") (pintype "input"))
      (node (ref "RaspberryPiPico2W") (pin "40") (pinfunction "VBUS_40") (pintype "unspecified"))
      (node (ref "U6") (pin "5") (pinfunction "VCC_5") (pintype "input"))
      (node (ref "USB1") (pin "A4-B9") (pinfunction "VBUS_A4-B9") (pintype "unspecified"))
      (node (ref "USB1") (pin "B4-A9") (pinfunction "VBUS_B4-A9") (pintype "unspecified"))
    )
    (net (code "3") (name "/OE") (class "Default")
      (node (ref "P1") (pin "1") (pinfunction "1_1") (pintype "input"))
      (node (ref "U6") (pin "1") (pinfunction "OE_1") (pintype "input"))
    )
    (net (code "4") (name "ADC0") (class "Default")
      (node (ref "RaspberryPiPico2W") (pin "31") (pinfunction "GP26_ADC0_I2C1SDA_31") (pintype "unspecified"))
    )
    (net (code "5") (name "ADC1") (class "Default")
      (node (ref "RaspberryPiPico2W") (pin "32") (pinfunction "GP27_ADC1_I2C1SCL_32") (pintype "unspecified"))
    )
    (net (code "6") (name "AGND") (class "Default")
      (node (ref "P3") (pin "2") (pinfunction "2_2") (pintype "input"))
      (node (ref "RaspberryPiPico2W") (pin "33") (pinfunction "GND_AGND_33") (pintype "unspecified"))
    )
    (net (code "7") (name "BOOT") (class "Default")
      (node (ref "Boot") (pin "1") (pinfunction "1_1") (pintype "unspecified"))
      (node (ref "RaspberryPiPico2W") (pin "TP6") (pinfunction "TP6_TP6") (pintype "unspecified"))
    )
    (net (code "8") (name "CENTERBUTTON") (class "Default")
      (node (ref "Encoder") (pin "D") (pinfunction "D_D") (pintype "unspecified"))
      (node (ref "RaspberryPiPico2W") (pin "19") (pinfunction "GP14_SPI1SCK_I2C1SDA_19") (pintype "unspecified"))
    )
    (net (code "9") (name "COLOM1") (class "Default")
      (node (ref "RaspberryPiPico2W") (pin "11") (pinfunction "GP8_SPI1RX_I2C0SDA_UART1TX_11") (pintype "unspecified"))
      (node (ref "S1") (pin "1") (pinfunction "1_1") (pintype "input"))
      (node (ref "S2") (pin "1") (pinfunction "1_1") (pintype "input"))
      (node (ref "S3") (pin "1") (pinfunction "1_1") (pintype "input"))
      (node (ref "S4") (pin "1") (pinfunction "1_1") (pintype "input"))
    )
    (net (code "10") (name "COLOM2") (class "Default")
      (node (ref "RaspberryPiPico2W") (pin "10") (pinfunction "GP7_SPI0TX_I2C1SCL_10") (pintype "unspecified"))
      (node (ref "S5") (pin "1") (pinfunction "1_1") (pintype "input"))
      (node (ref "S6") (pin "1") (pinfunction "1_1") (pintype "input"))
      (node (ref "S7") (pin "1") (pinfunction "1_1") (pintype "input"))
      (node (ref "S8") (pin "1") (pinfunction "1_1") (pintype "input"))
    )
    (net (code "11") (name "COLOM3") (class "Default")
      (node (ref "RaspberryPiPico2W") (pin "9") (pinfunction "GP6_SPI0SCK_I2C1SDA_9") (pintype "unspecified"))
      (node (ref "S10") (pin "1") (pinfunction "1_1") (pintype "input"))
      (node (ref "S11") (pin "1") (pinfunction "1_1") (pintype "input"))
      (node (ref "S12") (pin "1") (pinfunction "1_1") (pintype "input"))
      (node (ref "S9") (pin "1") (pinfunction "1_1") (pintype "input"))
    )
    (net (code "12") (name "COLOM4") (class "Default")
      (node (ref "RaspberryPiPico2W") (pin "7") (pinfunction "GP5_SPI0CSn_I2C0SCL_UART1RX_7") (pintype "unspecified"))
      (node (ref "S13") (pin "1") (pinfunction "1_1") (pintype "input"))
      (node (ref "S14") (pin "1") (pinfunction "1_1") (pintype "input"))
      (node (ref "S15") (pin "1") (pinfunction "1_1") (pintype "input"))
      (node (ref "S16") (pin "1") (pinfunction "1_1") (pintype "input"))
    )
    (net (code "13") (name "COLOM5") (class "Default")
      (node (ref "RaspberryPiPico2W") (pin "6") (pinfunction "GP4_SPI0RX_I2C0SDA_UART1TX_6") (pintype "unspecified"))
      (node (ref "S17") (pin "1") (pinfunction "1_1") (pintype "input"))
      (node (ref "S18") (pin "1") (pinfunction "1_1") (pintype "input"))
      (node (ref "S19") (pin "1") (pinfunction "1_1") (pintype "input"))
      (node (ref "S20") (pin "1") (pinfunction "1_1") (pintype "input"))
    )
    (net (code "14") (name "D+") (class "Default")
      (node (ref "RaspberryPiPico2W") (pin "TP3") (pinfunction "TP3_TP3") (pintype "unspecified"))
      (node (ref "USB1") (pin "A6") (pinfunction "Dp1_A6") (pintype "unspecified"))
      (node (ref "USB1") (pin "B6") (pinfunction "Dp2_B6") (pintype "unspecified"))
    )
    (net (code "15") (name "D-") (class "Default")
      (node (ref "RaspberryPiPico2W") (pin "TP2") (pinfunction "TP2_TP2") (pintype "unspecified"))
      (node (ref "USB1") (pin "A7") (pinfunction "Dn1_A7") (pintype "unspecified"))
      (node (ref "USB1") (pin "B7") (pinfunction "Dn2_B7") (pintype "unspecified"))
    )
    (net (code "16") (name "GND") (class "Default")
      (node (ref "Boot") (pin "2") (pinfunction "2_2") (pintype "unspecified"))
      (node (ref "C21") (pin "2") (pinfunction "2_2") (pintype "unspecified"))
      (node (ref "C22") (pin "2") (pinfunction "2_2") (pintype "unspecified"))
      (node (ref "C23") (pin "2") (pinfunction "2_2") (pintype "unspecified"))
      (node (ref "C24") (pin "2") (pinfunction "2_2") (pintype "unspecified"))
      (node (ref "C25") (pin "2") (pinfunction "2_2") (pintype "unspecified"))
      (node (ref "C26") (pin "2") (pinfunction "2_2") (pintype "unspecified"))
      (node (ref "C27") (pin "2") (pinfunction "2_2") (pintype "unspecified"))
      (node (ref "C28") (pin "2") (pinfunction "2_2") (pintype "unspecified"))
      (node (ref "C29") (pin "2") (pinfunction "2_2") (pintype "unspecified"))
      (node (ref "C30") (pin "2") (pinfunction "2_2") (pintype "unspecified"))
      (node (ref "C31") (pin "2") (pinfunction "2_2") (pintype "unspecified"))
      (node (ref "C32") (pin "2") (pinfunction "2_2") (pintype "unspecified"))
      (node (ref "C33") (pin "2") (pinfunction "2_2") (pintype "unspecified"))
      (node (ref "C34") (pin "2") (pinfunction "2_2") (pintype "unspecified"))
      (node (ref "C35") (pin "2") (pinfunction "2_2") (pintype "unspecified"))
      (node (ref "C36") (pin "2") (pinfunction "2_2") (pintype "unspecified"))
      (node (ref "C37") (pin "2") (pinfunction "2_2") (pintype "unspecified"))
      (node (ref "C38") (pin "2") (pinfunction "2_2") (pintype "unspecified"))
      (node (ref "C39") (pin "2") (pinfunction "2_2") (pintype "unspecified"))
      (node (ref "C40") (pin "2") (pinfunction "2_2") (pintype "unspecified"))
      (node (ref "C41") (pin "1") (pinfunction "1_1") (pintype "input"))
      (node (ref "C42") (pin "1") (pinfunction "1_1") (pintype "input"))
      (node (ref "C43") (pin "1") (pinfunction "1_1") (pintype "unspecified"))
      (node (ref "Encoder") (pin "C") (pinfunction "C_C") (pintype "unspecified"))
      (node (ref "Encoder") (pin "E") (pinfunction "E_E") (pintype "unspecified"))
      (node (ref "LED21") (pin "3") (pinfunction "GND_3") (pintype "unspecified"))
      (node (ref "LED22") (pin "3") (pinfunction "GND_3") (pintype "unspecified"))
      (node (ref "LED23") (pin "3") (pinfunction "GND_3") (pintype "unspecified"))
      (node (ref "LED24") (pin "3") (pinfunction "GND_3") (pintype "unspecified"))
      (node (ref "LED25") (pin "3") (pinfunction "GND_3") (pintype "unspecified"))
      (node (ref "LED26") (pin "3") (pinfunction "GND_3") (pintype "unspecified"))
      (node (ref "LED27") (pin "3") (pinfunction "GND_3") (pintype "unspecified"))
      (node (ref "LED28") (pin "3") (pinfunction "GND_3") (pintype "unspecified"))
      (node (ref "LED29") (pin "3") (pinfunction "GND_3") (pintype "unspecified"))
      (node (ref "LED30") (pin "3") (pinfunction "GND_3") (pintype "unspecified"))
      (node (ref "LED31") (pin "3") (pinfunction "GND_3") (pintype "unspecified"))
      (node (ref "LED32") (pin "3") (pinfunction "GND_3") (pintype "unspecified"))
      (node (ref "LED33") (pin "3") (pinfunction "GND_3") (pintype "unspecified"))
      (node (ref "LED34") (pin "3") (pinfunction "GND_3") (pintype "unspecified"))
      (node (ref "LED35") (pin "3") (pinfunction "GND_3") (pintype "unspecified"))
      (node (ref "LED36") (pin "3") (pinfunction "GND_3") (pintype "unspecified"))
      (node (ref "LED37") (pin "3") (pinfunction "GND_3") (pintype "unspecified"))
      (node (ref "LED38") (pin "3") (pinfunction "GND_3") (pintype "unspecified"))
      (node (ref "LED39") (pin "3") (pinfunction "GND_3") (pintype "unspecified"))
      (node (ref "LED40") (pin "3") (pinfunction "GND_3") (pintype "unspecified"))
      (node (ref "OLED_Female_P") (pin "3") (pinfunction "3_3") (pintype "input"))
      (node (ref "P2") (pin "2") (pinfunction "2_2") (pintype "input"))
      (node (ref "R1") (pin "1") (pinfunction "1_1") (pintype "unspecified"))
      (node (ref "R2") (pin "1") (pinfunction "1_1") (pintype "unspecified"))
      (node (ref "RESET") (pin "2") (pinfunction "2_2") (pintype "unspecified"))
      (node (ref "RaspberryPiPico2W") (pin "13") (pinfunction "GND_13") (pintype "unspecified"))
      (node (ref "RaspberryPiPico2W") (pin "18") (pinfunction "GND_18") (pintype "unspecified"))
      (node (ref "RaspberryPiPico2W") (pin "23") (pinfunction "GND_23") (pintype "unspecified"))
      (node (ref "RaspberryPiPico2W") (pin "28") (pinfunction "GND_28") (pintype "unspecified"))
      (node (ref "RaspberryPiPico2W") (pin "3") (pinfunction "GND_3") (pintype "unspecified"))
      (node (ref "RaspberryPiPico2W") (pin "38") (pinfunction "GND_38") (pintype "unspecified"))
      (node (ref "RaspberryPiPico2W") (pin "8") (pinfunction "GND_8") (pintype "unspecified"))
      (node (ref "RaspberryPiPico2W") (pin "TP1") (pinfunction "TP1_TP1") (pintype "unspecified"))
      (node (ref "U6") (pin "3") (pinfunction "GND_3") (pintype "input"))
      (node (ref "USB1") (pin "1") (pinfunction "EH_1") (pintype "unspecified"))
      (node (ref "USB1") (pin "2") (pinfunction "EH_2") (pintype "unspecified"))
      (node (ref "USB1") (pin "3") (pinfunction "EH_3") (pintype "unspecified"))
      (node (ref "USB1") (pin "4") (pinfunction "EH_4") (pintype "unspecified"))
      (node (ref "USB1") (pin "A1-B12") (pinfunction "GND_A1-B12") (pintype "unspecified"))
      (node (ref "USB1") (pin "B1-A12") (pinfunction "GND_B1-A12") (pintype "unspecified"))
    )
    (net (code "17") (name "LED_3.3") (class "Default")
      (node (ref "C43") (pin "2") (pinfunction "2_2") (pintype "unspecified"))
      (node (ref "RaspberryPiPico2W") (pin "12") (pinfunction "GP9_SPI1CSn_I2C0SCL_UART1RX_12") (pintype "unspecified"))
      (node (ref "U6") (pin "2") (pinfunction "A_2") (pintype "input"))
    )
    (net (code "18") (name "LED_5") (class "Default")
      (node (ref "LED40") (pin "4") (pinfunction "DIN_4") (pintype "unspecified"))
      (node (ref "R5") (pin "2") (pinfunction "2_2") (pintype "unspecified"))
    )
    (net (code "19") (name "Net-(D1-C)") (class "Default")
      (node (ref "D1") (pin "1") (pinfunction "C_1") (pintype "unspecified"))
      (node (ref "S1") (pin "2") (pinfunction "2_2") (pintype "input"))
    )
    (net (code "20") (name "Net-(D2-C)") (class "Default")
      (node (ref "D2") (pin "1") (pinfunction "C_1") (pintype "unspecified"))
      (node (ref "S2") (pin "2") (pinfunction "2_2") (pintype "input"))
    )
    (net (code "21") (name "Net-(D3-C)") (class "Default")
      (node (ref "D3") (pin "1") (pinfunction "C_1") (pintype "unspecified"))
      (node (ref "S3") (pin "2") (pinfunction "2_2") (pintype "input"))
    )
    (net (code "22") (name "Net-(D4-C)") (class "Default")
      (node (ref "D4") (pin "1") (pinfunction "C_1") (pintype "unspecified"))
      (node (ref "S4") (pin "2") (pinfunction "2_2") (pintype "input"))
    )
    (net (code "23") (name "Net-(D5-C)") (class "Default")
      (node (ref "D5") (pin "1") (pinfunction "C_1") (pintype "unspecified"))
      (node (ref "S5") (pin "2") (pinfunction "2_2") (pintype "input"))
    )
    (net (code "24") (name "Net-(D6-C)") (class "Default")
      (node (ref "D6") (pin "1") (pinfunction "C_1") (pintype "unspecified"))
      (node (ref "S6") (pin "2") (pinfunction "2_2") (pintype "input"))
    )
    (net (code "25") (name "Net-(D7-C)") (class "Default")
      (node (ref "D7") (pin "1") (pinfunction "C_1") (pintype "unspecified"))
      (node (ref "S7") (pin "2") (pinfunction "2_2") (pintype "input"))
    )
    (net (code "26") (name "Net-(D8-C)") (class "Default")
      (node (ref "D8") (pin "1") (pinfunction "C_1") (pintype "unspecified"))
      (node (ref "S8") (pin "2") (pinfunction "2_2") (pintype "input"))
    )
    (net (code "27") (name "Net-(D9-C)") (class "Default")
      (node (ref "D9") (pin "1") (pinfunction "C_1") (pintype "unspecified"))
      (node (ref "S9") (pin "2") (pinfunction "2_2") (pintype "input"))
    )
    (net (code "28") (name "Net-(D10-C)") (class "Default")
      (node (ref "D10") (pin "1") (pinfunction "C_1") (pintype "unspecified"))
      (node (ref "S10") (pin "2") (pinfunction "2_2") (pintype "input"))
    )
    (net (code "29") (name "Net-(D11-C)") (class "Default")
      (node (ref "D11") (pin "1") (pinfunction "C_1") (pintype "unspecified"))
      (node (ref "S11") (pin "2") (pinfunction "2_2") (pintype "input"))
    )
    (net (code "30") (name "Net-(D12-C)") (class "Default")
      (node (ref "D12") (pin "1") (pinfunction "C_1") (pintype "unspecified"))
      (node (ref "S12") (pin "2") (pinfunction "2_2") (pintype "input"))
    )
    (net (code "31") (name "Net-(D13-C)") (class "Default")
      (node (ref "D13") (pin "1") (pinfunction "C_1") (pintype "unspecified"))
      (node (ref "S13") (pin "2") (pinfunction "2_2") (pintype "input"))
    )
    (net (code "32") (name "Net-(D14-C)") (class "Default")
      (node (ref "D14") (pin "1") (pinfunction "C_1") (pintype "unspecified"))
      (node (ref "S14") (pin "2") (pinfunction "2_2") (pintype "input"))
    )
    (net (code "33") (name "Net-(D15-C)") (class "Default")
      (node (ref "D15") (pin "1") (pinfunction "C_1") (pintype "unspecified"))
      (node (ref "S15") (pin "2") (pinfunction "2_2") (pintype "input"))
    )
    (net (code "34") (name "Net-(D16-C)") (class "Default")
      (node (ref "D16") (pin "1") (pinfunction "C_1") (pintype "unspecified"))
      (node (ref "S16") (pin "2") (pinfunction "2_2") (pintype "input"))
    )
    (net (code "35") (name "Net-(D17-C)") (class "Default")
      (node (ref "D17") (pin "1") (pinfunction "C_1") (pintype "unspecified"))
      (node (ref "S17") (pin "2") (pinfunction "2_2") (pintype "input"))
    )
    (net (code "36") (name "Net-(D18-C)") (class "Default")
      (node (ref "D18") (pin "1") (pinfunction "C_1") (pintype "unspecified"))
      (node (ref "S18") (pin "2") (pinfunction "2_2") (pintype "input"))
    )
    (net (code "37") (name "Net-(D19-C)") (class "Default")
      (node (ref "D19") (pin "1") (pinfunction "C_1") (pintype "unspecified"))
      (node (ref "S19") (pin "2") (pinfunction "2_2") (pintype "input"))
    )
    (net (code "38") (name "Net-(D20-C)") (class "Default")
      (node (ref "D20") (pin "1") (pinfunction "C_1") (pintype "unspecified"))
      (node (ref "S20") (pin "2") (pinfunction "2_2") (pintype "input"))
    )
    (net (code "39") (name "Net-(LED21-DIN)") (class "Default")
      (node (ref "LED21") (pin "4") (pinfunction "DIN_4") (pintype "unspecified"))
      (node (ref "LED22") (pin "2") (pinfunction "DOUT_2") (pintype "unspecified"))
    )
    (net (code "40") (name "Net-(LED22-DIN)") (class "Default")
      (node (ref "LED22") (pin "4") (pinfunction "DIN_4") (pintype "unspecified"))
      (node (ref "LED23") (pin "2") (pinfunction "DOUT_2") (pintype "unspecified"))
    )
    (net (code "41") (name "Net-(LED23-DIN)") (class "Default")
      (node (ref "LED23") (pin "4") (pinfunction "DIN_4") (pintype "unspecified"))
      (node (ref "LED24") (pin "2") (pinfunction "DOUT_2") (pintype "unspecified"))
    )
    (net (code "42") (name "Net-(LED24-DIN)") (class "Default")
      (node (ref "LED24") (pin "4") (pinfunction "DIN_4") (pintype "unspecified"))
      (node (ref "LED25") (pin "2") (pinfunction "DOUT_2") (pintype "unspecified"))
    )
    (net (code "43") (name "Net-(LED25-DIN)") (class "Default")
      (node (ref "LED25") (pin "4") (pinfunction "DIN_4") (pintype "unspecified"))
      (node (ref "LED26") (pin "2") (pinfunction "DOUT_2") (pintype "unspecified"))
    )
    (net (code "44") (name "Net-(LED26-DIN)") (class "Default")
      (node (ref "LED26") (pin "4") (pinfunction "DIN_4") (pintype "unspecified"))
      (node (ref "LED27") (pin "2") (pinfunction "DOUT_2") (pintype "unspecified"))
    )
    (net (code "45") (name "Net-(LED27-DIN)") (class "Default")
      (node (ref "LED27") (pin "4") (pinfunction "DIN_4") (pintype "unspecified"))
      (node (ref "LED28") (pin "2") (pinfunction "DOUT_2") (pintype "unspecified"))
    )
    (net (code "46") (name "Net-(LED28-DIN)") (class "Default")
      (node (ref "LED28") (pin "4") (pinfunction "DIN_4") (pintype "unspecified"))
      (node (ref "LED29") (pin "2") (pinfunction "DOUT_2") (pintype "unspecified"))
    )
    (net (code "47") (name "Net-(LED29-DIN)") (class "Default")
      (node (ref "LED29") (pin "4") (pinfunction "DIN_4") (pintype "unspecified"))
      (node (ref "LED30") (pin "2") (pinfunction "DOUT_2") (pintype "unspecified"))
    )
    (net (code "48") (name "Net-(LED30-DIN)") (class "Default")
      (node (ref "LED30") (pin "4") (pinfunction "DIN_4") (pintype "unspecified"))
      (node (ref "LED31") (pin "2") (pinfunction "DOUT_2") (pintype "unspecified"))
    )
    (net (code "49") (name "Net-(LED31-DIN)") (class "Default")
      (node (ref "LED31") (pin "4") (pinfunction "DIN_4") (pintype "unspecified"))
      (node (ref "LED32") (pin "2") (pinfunction "DOUT_2") (pintype "unspecified"))
    )
    (net (code "50") (name "Net-(LED32-DIN)") (class "Default")
      (node (ref "LED32") (pin "4") (pinfunction "DIN_4") (pintype "unspecified"))
      (node (ref "LED33") (pin "2") (pinfunction "DOUT_2") (pintype "unspecified"))
    )
    (net (code "51") (name "Net-(LED33-DIN)") (class "Default")
      (node (ref "LED33") (pin "4") (pinfunction "DIN_4") (pintype "unspecified"))
      (node (ref "LED34") (pin "2") (pinfunction "DOUT_2") (pintype "unspecified"))
    )
    (net (code "52") (name "Net-(LED34-DIN)") (class "Default")
      (node (ref "LED34") (pin "4") (pinfunction "DIN_4") (pintype "unspecified"))
      (node (ref "LED35") (pin "2") (pinfunction "DOUT_2") (pintype "unspecified"))
    )
    (net (code "53") (name "Net-(LED35-DIN)") (class "Default")
      (node (ref "LED35") (pin "4") (pinfunction "DIN_4") (pintype "unspecified"))
      (node (ref "LED36") (pin "2") (pinfunction "DOUT_2") (pintype "unspecified"))
    )
    (net (code "54") (name "Net-(LED36-DIN)") (class "Default")
      (node (ref "LED36") (pin "4") (pinfunction "DIN_4") (pintype "unspecified"))
      (node (ref "LED37") (pin "2") (pinfunction "DOUT_2") (pintype "unspecified"))
    )
    (net (code "55") (name "Net-(LED37-DIN)") (class "Default")
      (node (ref "LED37") (pin "4") (pinfunction "DIN_4") (pintype "unspecified"))
      (node (ref "LED38") (pin "2") (pinfunction "DOUT_2") (pintype "unspecified"))
    )
    (net (code "56") (name "Net-(LED38-DIN)") (class "Default")
      (node (ref "LED38") (pin "4") (pinfunction "DIN_4") (pintype "unspecified"))
      (node (ref "LED39") (pin "2") (pinfunction "DOUT_2") (pintype "unspecified"))
    )
    (net (code "57") (name "Net-(LED39-DIN)") (class "Default")
      (node (ref "LED39") (pin "4") (pinfunction "DIN_4") (pintype "unspecified"))
      (node (ref "LED40") (pin "2") (pinfunction "DOUT_2") (pintype "unspecified"))
    )
    (net (code "58") (name "Net-(P2-Pad1)") (class "Default")
      (node (ref "P2") (pin "1") (pinfunction "1_1") (pintype "input"))
      (node (ref "P3") (pin "1") (pinfunction "1_1") (pintype "input"))
      (node (ref "Volume_Slider") (pin "1") (pinfunction "1_1") (pintype "unspecified"))
    )
    (net (code "59") (name "Net-(U6-Y)") (class "Default")
      (node (ref "R5") (pin "1") (pinfunction "1_1") (pintype "unspecified"))
      (node (ref "U6") (pin "4") (pinfunction "Y_4") (pintype "input"))
    )
    (net (code "60") (name "Net-(USB1-CC1)") (class "Default")
      (node (ref "R1") (pin "2") (pinfunction "2_2") (pintype "unspecified"))
      (node (ref "USB1") (pin "A5") (pinfunction "CC1_A5") (pintype "unspecified"))
    )
    (net (code "61") (name "Net-(USB1-CC2)") (class "Default")
      (node (ref "R2") (pin "2") (pinfunction "2_2") (pintype "unspecified"))
      (node (ref "USB1") (pin "B5") (pinfunction "CC2_B5") (pintype "unspecified"))
    )
    (net (code "62") (name "RESET") (class "Default")
      (node (ref "RESET") (pin "1") (pinfunction "1_1") (pintype "unspecified"))
      (node (ref "RaspberryPiPico2W") (pin "30") (pinfunction "RUN_30") (pintype "unspecified"))
    )
    (net (code "63") (name "ROW1") (class "Default")
      (node (ref "D1") (pin "2") (pinfunction "A_2") (pintype "unspecified"))
      (node (ref "D13") (pin "2") (pinfunction "A_2") (pintype "unspecified"))
      (node (ref "D17") (pin "2") (pinfunction "A_2") (pintype "unspecified"))
      (node (ref "D5") (pin "2") (pinfunction "A_2") (pintype "unspecified"))
      (node (ref "D9") (pin "2") (pinfunction "A_2") (pintype "unspecified"))
      (node (ref "RaspberryPiPico2W") (pin "1") (pinfunction "GP0_SPI0RX_I2C0SDA_UART0TX_1") (pintype "unspecified"))
    )
    (net (code "64") (name "ROW2") (class "Default")
      (node (ref "D10") (pin "2") (pinfunction "A_2") (pintype "unspecified"))
      (node (ref "D14") (pin "2") (pinfunction "A_2") (pintype "unspecified"))
      (node (ref "D18") (pin "2") (pinfunction "A_2") (pintype "unspecified"))
      (node (ref "D2") (pin "2") (pinfunction "A_2") (pintype "unspecified"))
      (node (ref "D6") (pin "2") (pinfunction "A_2") (pintype "unspecified"))
      (node (ref "RaspberryPiPico2W") (pin "2") (pinfunction "GP1_SPI0CSn_I2C0SCL_UART0RX_2") (pintype "unspecified"))
    )
    (net (code "65") (name "ROW3") (class "Default")
      (node (ref "D11") (pin "2") (pinfunction "A_2") (pintype "unspecified"))
      (node (ref "D15") (pin "2") (pinfunction "A_2") (pintype "unspecified"))
      (node (ref "D19") (pin "2") (pinfunction "A_2") (pintype "unspecified"))
      (node (ref "D3") (pin "2") (pinfunction "A_2") (pintype "unspecified"))
      (node (ref "D7") (pin "2") (pinfunction "A_2") (pintype "unspecified"))
      (node (ref "RaspberryPiPico2W") (pin "4") (pinfunction "GP2_SPI0SCK_I2C1SDA_4") (pintype "unspecified"))
    )
    (net (code "66") (name "ROW4") (class "Default")
      (node (ref "D12") (pin "2") (pinfunction "A_2") (pintype "unspecified"))
      (node (ref "D16") (pin "2") (pinfunction "A_2") (pintype "unspecified"))
      (node (ref "D20") (pin "2") (pinfunction "A_2") (pintype "unspecified"))
      (node (ref "D4") (pin "2") (pinfunction "A_2") (pintype "unspecified"))
      (node (ref "D8") (pin "2") (pinfunction "A_2") (pintype "unspecified"))
      (node (ref "RaspberryPiPico2W") (pin "5") (pinfunction "GP3_SPI0TX_I2C1SCL_5") (pintype "unspecified"))
    )
    (net (code "67") (name "SCL") (class "Default")
      (node (ref "RaspberryPiPico2W") (pin "17") (pinfunction "GP13_SPI1CSn_I2C0SCL_UART0RX_17") (pintype "unspecified"))
    )
    (net (code "68") (name "SCL1") (class "Default")
      (node (ref "OLED_Female_P") (pin "2") (pinfunction "2_2") (pintype "input"))
      (node (ref "RaspberryPiPico2W") (pin "27") (pinfunction "GP21_I2C0SCL_27") (pintype "unspecified"))
    )
    (net (code "69") (name "SDA") (class "Default")
      (node (ref "RaspberryPiPico2W") (pin "16") (pinfunction "GP12_SPI1RX_I2C0SDA_UART0TX_16") (pintype "unspecified"))
    )
    (net (code "70") (name "SDA1") (class "Default")
      (node (ref "OLED_Female_P") (pin "1") (pinfunction "1_1") (pintype "input"))
      (node (ref "RaspberryPiPico2W") (pin "26") (pinfunction "GP20_I2C0SDA_26") (pintype "unspecified"))
    )
    (net (code "71") (name "SLIDER") (class "Default")
      (node (ref "RaspberryPiPico2W") (pin "34") (pinfunction "GP28_ADC2_34") (pintype "unspecified"))
      (node (ref "Volume_Slider") (pin "2") (pinfunction "2_2") (pintype "unspecified"))
    )
    (net (code "72") (name "SW1A") (class "Default")
      (node (ref "C42") (pin "2") (pinfunction "2_2") (pintype "input"))
      (node (ref "Encoder") (pin "A") (pinfunction "A_A") (pintype "unspecified"))
      (node (ref "R4") (pin "2") (pinfunction "2_2") (pintype "unspecified"))
      (node (ref "RaspberryPiPico2W") (pin "14") (pinfunction "GP10_SPI1SCK_I2C1SDA_14") (pintype "unspecified"))
    )
    (net (code "73") (name "SW1B") (class "Default")
      (node (ref "C41") (pin "2") (pinfunction "2_2") (pintype "input"))
      (node (ref "Encoder") (pin "B") (pinfunction "B_B") (pintype "unspecified"))
      (node (ref "R3") (pin "1") (pinfunction "1_1") (pintype "unspecified"))
      (node (ref "RaspberryPiPico2W") (pin "15") (pinfunction "GP11_SPI1TX_I2C1SCL_15") (pintype "unspecified"))
    )
    (net (code "74") (name "unconnected-(Encoder-Pad6)") (class "Default")
      (node (ref "Encoder") (pin "6") (pinfunction "6_6") (pintype "unspecified+no_connect"))
    )
    (net (code "75") (name "unconnected-(Encoder-Pad7)") (class "Default")
      (node (ref "Encoder") (pin "7") (pinfunction "7_7") (pintype "unspecified+no_connect"))
    )
    (net (code "76") (name "unconnected-(LED21-DOUT-Pad2)") (class "Default")
      (node (ref "LED21") (pin "2") (pinfunction "DOUT_2") (pintype "unspecified"))
    )
    (net (code "77") (name "unconnected-(RaspberryPiPico2W-3V3_EN-Pad37)") (class "Default")
      (node (ref "RaspberryPiPico2W") (pin "37") (pinfunction "3V3_EN_37") (pintype "unspecified"))
    )
    (net (code "78") (name "unconnected-(RaspberryPiPico2W-ADC_VREF-Pad35)") (class "Default")
      (node (ref "RaspberryPiPico2W") (pin "35") (pinfunction "ADC_VREF_35") (pintype "unspecified"))
    )
    (net (code "79") (name "unconnected-(RaspberryPiPico2W-GP15_SPI1TX_I2C1SCL-Pad20)") (class "Default")
      (node (ref "RaspberryPiPico2W") (pin "20") (pinfunction "GP15_SPI1TX_I2C1SCL_20") (pintype "unspecified"))
    )
    (net (code "80") (name "unconnected-(RaspberryPiPico2W-GP16_SPI0RX_UART0RX-Pad21)") (class "Default")
      (node (ref "RaspberryPiPico2W") (pin "21") (pinfunction "GP16_SPI0RX_UART0RX_21") (pintype "unspecified"))
    )
    (net (code "81") (name "unconnected-(RaspberryPiPico2W-GP17_SPI0CSn_UART0TX-Pad22)") (class "Default")
      (node (ref "RaspberryPiPico2W") (pin "22") (pinfunction "GP17_SPI0CSn_UART0TX_22") (pintype "unspecified"))
    )
    (net (code "82") (name "unconnected-(RaspberryPiPico2W-GP18_SPI0SCK_I2C1SDA-Pad24)") (class "Default")
      (node (ref "RaspberryPiPico2W") (pin "24") (pinfunction "GP18_SPI0SCK_I2C1SDA_24") (pintype "unspecified"))
    )
    (net (code "83") (name "unconnected-(RaspberryPiPico2W-GP19_SPI0TX_I2C1SCL-Pad25)") (class "Default")
      (node (ref "RaspberryPiPico2W") (pin "25") (pinfunction "GP19_SPI0TX_I2C1SCL_25") (pintype "unspecified"))
    )
    (net (code "84") (name "unconnected-(RaspberryPiPico2W-GP22-Pad29)") (class "Default")
      (node (ref "RaspberryPiPico2W") (pin "29") (pinfunction "GP22_29") (pintype "unspecified"))
    )
    (net (code "85") (name "unconnected-(RaspberryPiPico2W-PadTP4)") (class "Default")
      (node (ref "RaspberryPiPico2W") (pin "TP4") (pinfunction "TP4_TP4") (pintype "unspecified"))
    )
    (net (code "86") (name "unconnected-(RaspberryPiPico2W-PadTP5)") (class "Default")
      (node (ref "RaspberryPiPico2W") (pin "TP5") (pinfunction "TP5_TP5") (pintype "unspecified"))
    )
    (net (code "87") (name "unconnected-(RaspberryPiPico2W-VSYS-Pad39)") (class "Default")
      (node (ref "RaspberryPiPico2W") (pin "39") (pinfunction "VSYS_39") (pintype "unspecified"))
    )
    (net (code "88") (name "unconnected-(USB1-SBU1-PadA8)") (class "Default")
      (node (ref "USB1") (pin "A8") (pinfunction "SBU1_A8") (pintype "unspecified+no_connect"))
    )
    (net (code "89") (name "unconnected-(USB1-SBU2-PadB8)") (class "Default")
      (node (ref "USB1") (pin "B8") (pinfunction "SBU2_B8") (pintype "unspecified+no_connect"))
    )
    (net (code "90") (name "unconnected-(Volume_Slider-Pad4)") (class "Default")
      (node (ref "Volume_Slider") (pin "4") (pinfunction "4_4") (pintype "unspecified+no_connect"))
    )
    (net (code "91") (name "unconnected-(Volume_Slider-Pad5)") (class "Default")
      (node (ref "Volume_Slider") (pin "5") (pinfunction "5_5") (pintype "unspecified+no_connect"))
    )
    (net (code "92") (name "unconnected-(Volume_Slider-Pad6)") (class "Default")
      (node (ref "Volume_Slider") (pin "6") (pinfunction "6_6") (pintype "unspecified+no_connect"))
    )
    (net (code "93") (name "unconnected-(Volume_Slider-Pad7)") (class "Default")
      (node (ref "Volume_Slider") (pin "7") (pinfunction "7_7") (pintype "unspecified+no_connect"))
    )
  )
)
